# Sheet1_GMAX0505_2518_MB.net
KiCad netlist of a schematic drawn in Altium Designer
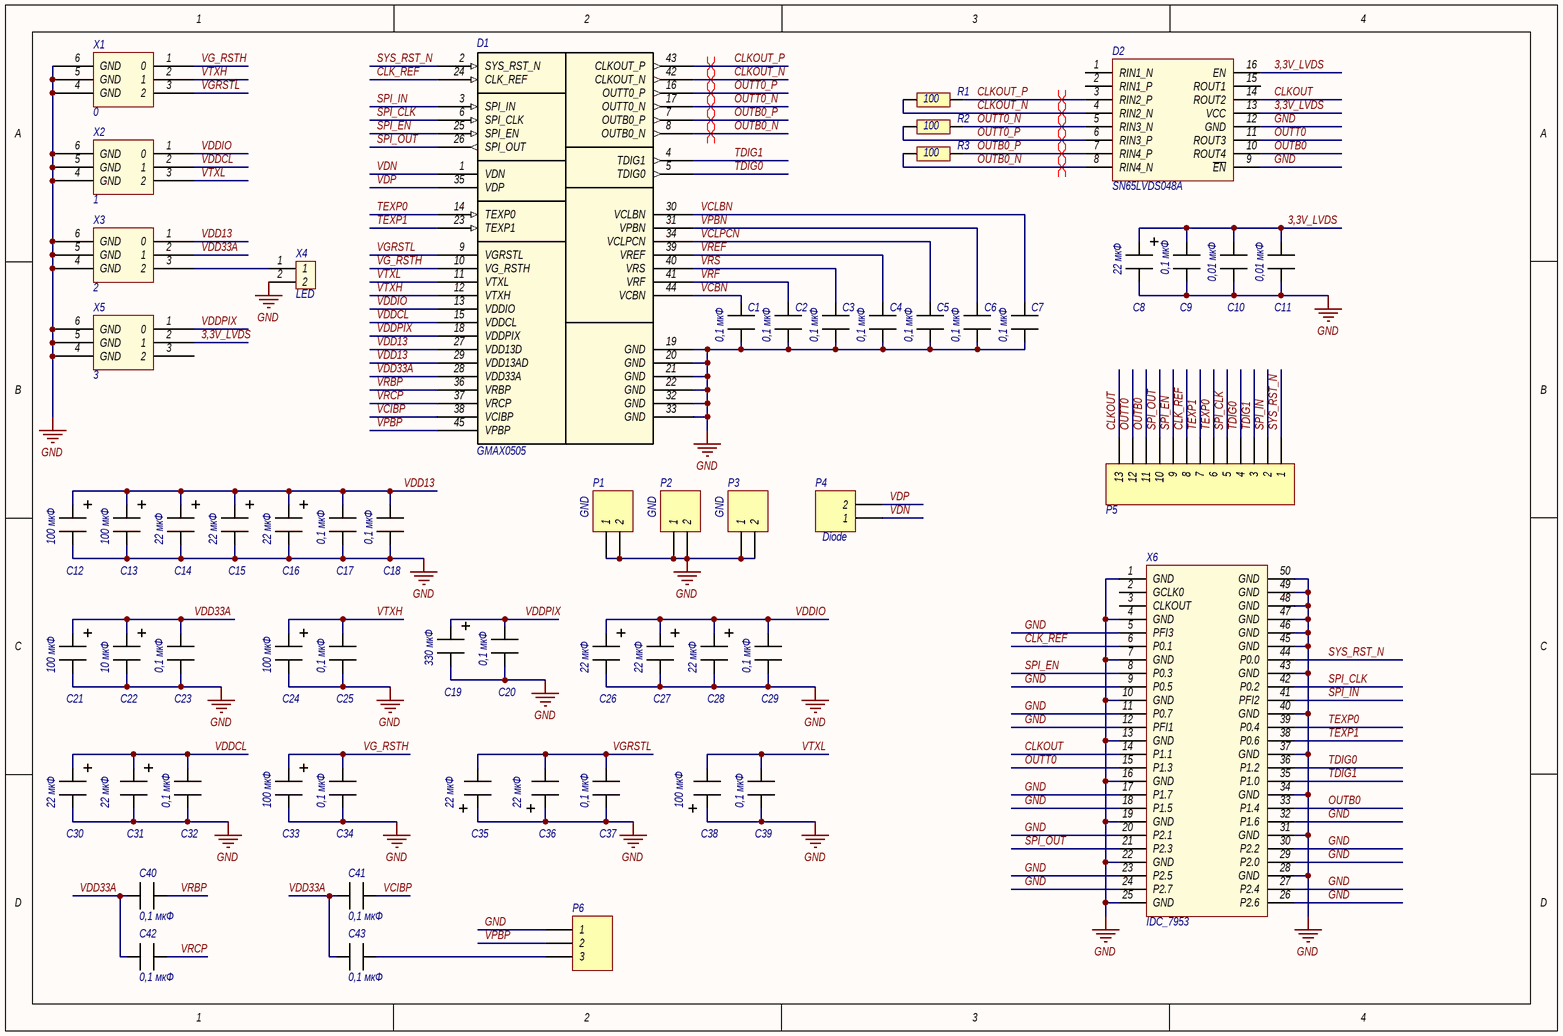
[diagram p0: Sheet1_GMAX0505_2518_MB.SchDoc]

(export (version "E")
  (design (tool "Eeschema 10.0.6"))
  (components
    (comp (ref "C1") (value "0,1 мкФ") (footprint "CAP_SMALL") (libsource (lib "Schlib") (part "CAP_SMALL")))
    (comp (ref "C2") (value "0,1 мкФ") (footprint "CAP_SMALL") (libsource (lib "Schlib") (part "CAP_SMALL")))
    (comp (ref "C3") (value "0,1 мкФ") (footprint "CAP_SMALL") (libsource (lib "Schlib") (part "CAP_SMALL")))
    (comp (ref "C4") (value "0,1 мкФ") (footprint "CAP_SMALL") (libsource (lib "Schlib") (part "CAP_SMALL")))
    (comp (ref "C5") (value "0,1 мкФ") (footprint "CAP_SMALL") (libsource (lib "Schlib") (part "CAP_SMALL")))
    (comp (ref "C6") (value "0,1 мкФ") (footprint "CAP_SMALL") (libsource (lib "Schlib") (part "CAP_SMALL")))
    (comp (ref "C7") (value "0,1 мкФ") (footprint "CAP_SMALL") (libsource (lib "Schlib") (part "CAP_SMALL")))
    (comp (ref "C8")
      (value "22 мкФ")
      (footprint "Cap_0511_electrolitic")
      (libsource (lib "Schlib") (part "Cap_electrolotoc_0511"))
    )
    (comp (ref "C9") (value "0,1 мкФ") (footprint "CAP_SMALL") (libsource (lib "Schlib") (part "CAP_SMALL")))
    (comp (ref "C10")
      (value "0,01 мкФ")
      (footprint "CAP_SMALL")
      (libsource (lib "Schlib") (part "CAP_SMALL"))
    )
    (comp (ref "C11")
      (value "0,01 мкФ")
      (footprint "CAP_SMALL")
      (libsource (lib "Schlib") (part "CAP_SMALL"))
    )
    (comp (ref "C12")
      (value "100 мкФ")
      (footprint "Cap_0612_electrolitic")
      (libsource (lib "Schlib") (part "Cap_electrolotoc_0612"))
    )
    (comp (ref "C13")
      (value "100 мкФ")
      (footprint "Cap_0612_electrolitic")
      (libsource (lib "Schlib") (part "Cap_electrolotoc_0612"))
    )
    (comp (ref "C14")
      (value "22 мкФ")
      (footprint "Cap_0511_electrolitic")
      (libsource (lib "Schlib") (part "Cap_electrolotoc_0511"))
    )
    (comp (ref "C15")
      (value "22 мкФ")
      (footprint "Cap_0511_electrolitic")
      (libsource (lib "Schlib") (part "Cap_electrolotoc_0511"))
    )
    (comp (ref "C16")
      (value "22 мкФ")
      (footprint "Cap_0511_electrolitic")
      (libsource (lib "Schlib") (part "Cap_electrolotoc_0511"))
    )
    (comp (ref "C17") (value "0,1 мкФ") (footprint "CAP_SMALL") (libsource (lib "Schlib") (part "CAP_SMALL")))
    (comp (ref "C18") (value "0,1 мкФ") (footprint "CAP_SMALL") (libsource (lib "Schlib") (part "CAP_SMALL")))
    (comp (ref "C19")
      (value "330 мкФ")
      (footprint "Cap_1013_electrolitic")
      (libsource (lib "Schlib") (part "Cap_electrolotoc_1013"))
    )
    (comp (ref "C20") (value "0,1 мкФ") (footprint "CAP_SMALL") (libsource (lib "Schlib") (part "CAP_SMALL")))
    (comp (ref "C21")
      (value "100 мкФ")
      (footprint "Cap_0612_electrolitic")
      (libsource (lib "Schlib") (part "Cap_electrolotoc_0612"))
    )
    (comp (ref "C22")
      (value "10 мкФ")
      (footprint "Cap_0511_electrolitic")
      (libsource (lib "Schlib") (part "Cap_electrolotoc_0511"))
    )
    (comp (ref "C23") (value "0,1 мкФ") (footprint "CAP_SMALL") (libsource (lib "Schlib") (part "CAP_SMALL")))
    (comp (ref "C24")
      (value "100 мкФ")
      (footprint "Cap_0612_electrolitic")
      (libsource (lib "Schlib") (part "Cap_electrolotoc_0612"))
    )
    (comp (ref "C25") (value "0,1 мкФ") (footprint "CAP_SMALL") (libsource (lib "Schlib") (part "CAP_SMALL")))
    (comp (ref "C26")
      (value "22 мкФ")
      (footprint "Cap_0511_electrolitic")
      (libsource (lib "Schlib") (part "Cap_electrolotoc_0511"))
    )
    (comp (ref "C27")
      (value "22 мкФ")
      (footprint "Cap_0511_electrolitic")
      (libsource (lib "Schlib") (part "Cap_electrolotoc_0511"))
    )
    (comp (ref "C28")
      (value "22 мкФ")
      (footprint "Cap_0511_electrolitic")
      (libsource (lib "Schlib") (part "Cap_electrolotoc_0511"))
    )
    (comp (ref "C29") (value "0,1 мкФ") (footprint "CAP_SMALL") (libsource (lib "Schlib") (part "CAP_SMALL")))
    (comp (ref "C30")
      (value "22 мкФ")
      (footprint "Cap_0511_electrolitic")
      (libsource (lib "Schlib") (part "Cap_electrolotoc_0511"))
    )
    (comp (ref "C31")
      (value "22 мкФ")
      (footprint "Cap_0511_electrolitic")
      (libsource (lib "Schlib") (part "Cap_electrolotoc_0511"))
    )
    (comp (ref "C32") (value "0,1 мкФ") (footprint "CAP_SMALL") (libsource (lib "Schlib") (part "CAP_SMALL")))
    (comp (ref "C33")
      (value "100 мкФ")
      (footprint "Cap_0612_electrolitic")
      (libsource (lib "Schlib") (part "Cap_electrolotoc_0612"))
    )
    (comp (ref "C34") (value "0,1 мкФ") (footprint "CAP_SMALL") (libsource (lib "Schlib") (part "CAP_SMALL")))
    (comp (ref "C35")
      (value "22 мкФ")
      (footprint "Cap_0511_electrolitic")
      (libsource (lib "Schlib") (part "Cap_electrolotoc_0511"))
    )
    (comp (ref "C36")
      (value "22 мкФ")
      (footprint "Cap_0511_electrolitic")
      (libsource (lib "Schlib") (part "Cap_electrolotoc_0511"))
    )
    (comp (ref "C37") (value "0,1 мкФ") (footprint "CAP_SMALL") (libsource (lib "Schlib") (part "CAP_SMALL")))
    (comp (ref "C38")
      (value "100 мкФ")
      (footprint "Cap_0612_electrolitic")
      (libsource (lib "Schlib") (part "Cap_electrolotoc_0612"))
    )
    (comp (ref "C39") (value "0,1 мкФ") (footprint "CAP_SMALL") (libsource (lib "Schlib") (part "CAP_SMALL")))
    (comp (ref "C40") (value "0,1 мкФ") (footprint "CAP_SMALL") (libsource (lib "Schlib") (part "CAP_SMALL")))
    (comp (ref "C41") (value "0,1 мкФ") (footprint "CAP_SMALL") (libsource (lib "Schlib") (part "CAP_SMALL")))
    (comp (ref "C42") (value "0,1 мкФ") (footprint "CAP_SMALL") (libsource (lib "Schlib") (part "CAP_SMALL")))
    (comp (ref "C43") (value "0,1 мкФ") (footprint "CAP_SMALL") (libsource (lib "Schlib") (part "CAP_SMALL")))
    (comp (ref "D1")
      (value "GMAX0505")
      (footprint "GMAX0505_MEZ")
      (libsource (lib "Schlib") (part "GMAX0505_MEZ"))
    )
    (comp (ref "D2")
      (value "SN65LVDS048A")
      (footprint "SN65LVDS048A (4LVDS)")
      (libsource (lib "Schlib") (part "SN65LVDS048A (4LVDS)"))
    )
    (comp (ref "P1")
      (value "GND")
      (footprint "HDR1X2")
      (description "Header, 2-Pin")
      (fields (field (name "PUBLISHER") "Altium Limited"))
      (libsource (lib "Miscellaneous Connectors") (part "Header 2"))
    )
    (comp (ref "P2")
      (value "GND")
      (footprint "HDR1X2")
      (description "Header, 2-Pin")
      (fields (field (name "PUBLISHER") "Altium Limited"))
      (libsource (lib "Miscellaneous Connectors") (part "Header 2"))
    )
    (comp (ref "P3")
      (value "GND")
      (footprint "HDR1X2")
      (description "Header, 2-Pin")
      (fields (field (name "PUBLISHER") "Altium Limited"))
      (libsource (lib "Miscellaneous Connectors") (part "Header 2"))
    )
    (comp (ref "P4")
      (value "Diode")
      (footprint "HDR1X2")
      (description "Header, 2-Pin")
      (fields (field (name "PUBLISHER") "Altium Limited"))
      (libsource (lib "") (part "Header 2_1"))
    )
    (comp (ref "P5")
      (value "Header 13")
      (footprint "HDR1X13")
      (description "Header, 13-Pin")
      (fields (field (name "PUBLISHER") "Altium Limited"))
      (libsource (lib "Miscellaneous Connectors") (part "Header 13"))
    )
    (comp (ref "P6")
      (value "VPBP")
      (footprint "HDR1X3")
      (description "Header, 3-Pin")
      (fields (field (name "PUBLISHER") "Altium Limited"))
      (libsource (lib "Miscellaneous Connectors") (part "Header 3"))
    )
    (comp (ref "R1") (value "100") (footprint "RES") (libsource (lib "Schlib") (part "RES")))
    (comp (ref "R2") (value "100") (footprint "RES") (libsource (lib "Schlib") (part "RES")))
    (comp (ref "R3") (value "100") (footprint "RES") (libsource (lib "Schlib") (part "RES")))
    (comp (ref "X1") (value "0") (footprint "POWER") (libsource (lib "Schlib") (part "POWER")))
    (comp (ref "X2") (value "1") (footprint "POWER") (libsource (lib "Schlib") (part "POWER")))
    (comp (ref "X3") (value "2") (footprint "POWER") (libsource (lib "Schlib") (part "POWER")))
    (comp (ref "X4") (value "LED") (footprint "KLEMMNIK_2") (libsource (lib "Schlib") (part "KLEMMNIK_2")))
    (comp (ref "X5") (value "3") (footprint "POWER") (libsource (lib "Schlib") (part "POWER")))
    (comp (ref "X6") (value "IDC_7953") (footprint "IDC_7953") (libsource (lib "VPL") (part "IDC_7953")))
  )
  (nets
    (net (code "1") (name "/3,3V_LVDS") (class "Default")
      (node (ref "C10") (pin "2") (pinfunction "2_2") (pintype "passive"))
      (node (ref "C11") (pin "2") (pinfunction "2_2") (pintype "passive"))
      (node (ref "C8") (pin "1") (pinfunction "1_1") (pintype "passive"))
      (node (ref "C9") (pin "2") (pinfunction "2_2") (pintype "passive"))
      (node (ref "D2") (pin "13") (pinfunction "VCC_13") (pintype "passive"))
      (node (ref "D2") (pin "16") (pinfunction "EN_16") (pintype "passive"))
      (node (ref "X5") (pin "2") (pinfunction "1_2") (pintype "passive"))
    )
    (net (code "2") (name "/CLKOUT") (class "Default")
      (node (ref "D2") (pin "14") (pinfunction "ROUT2_14") (pintype "passive"))
      (node (ref "P5") (pin "13") (pinfunction "13_13") (pintype "passive"))
      (node (ref "X6") (pin "14") (pinfunction "P1.1_14") (pintype "passive"))
    )
    (net (code "3") (name "/CLKOUT_N") (class "Default")
      (node (ref "D1") (pin "42") (pinfunction "CLKOUT_N_42") (pintype "output"))
      (node (ref "D2") (pin "4") (pinfunction "RIN2_N_4") (pintype "passive"))
      (node (ref "R1") (pin "2") (pinfunction "2_2") (pintype "passive"))
    )
    (net (code "4") (name "/CLKOUT_P") (class "Default")
      (node (ref "D1") (pin "43") (pinfunction "CLKOUT_P_43") (pintype "output"))
      (node (ref "D2") (pin "3") (pinfunction "RIN2_P_3") (pintype "passive"))
      (node (ref "R1") (pin "1") (pinfunction "1_1") (pintype "passive"))
    )
    (net (code "5") (name "/CLK_REF") (class "Default")
      (node (ref "D1") (pin "24") (pinfunction "CLK_REF_24") (pintype "input"))
      (node (ref "P5") (pin "8") (pinfunction "8_8") (pintype "passive"))
      (node (ref "X6") (pin "6") (pinfunction "P0.1_6") (pintype "passive"))
    )
    (net (code "6") (name "/OUTB0") (class "Default")
      (node (ref "D2") (pin "10") (pinfunction "ROUT4_10") (pintype "passive"))
      (node (ref "P5") (pin "11") (pinfunction "11_11") (pintype "passive"))
      (node (ref "X6") (pin "33") (pinfunction "P1.4_33") (pintype "passive"))
    )
    (net (code "7") (name "/OUTB0_N") (class "Default")
      (node (ref "D1") (pin "8") (pinfunction "OUTB0_N_8") (pintype "output"))
      (node (ref "D2") (pin "8") (pinfunction "RIN4_N_8") (pintype "passive"))
      (node (ref "R3") (pin "2") (pinfunction "2_2") (pintype "passive"))
    )
    (net (code "8") (name "/OUTB0_P") (class "Default")
      (node (ref "D1") (pin "7") (pinfunction "OUTB0_P_7") (pintype "output"))
      (node (ref "D2") (pin "7") (pinfunction "RIN4_P_7") (pintype "passive"))
      (node (ref "R3") (pin "1") (pinfunction "1_1") (pintype "passive"))
    )
    (net (code "9") (name "/OUTT0") (class "Default")
      (node (ref "D2") (pin "11") (pinfunction "ROUT3_11") (pintype "passive"))
      (node (ref "P5") (pin "12") (pinfunction "12_12") (pintype "passive"))
      (node (ref "X6") (pin "15") (pinfunction "P1.3_15") (pintype "passive"))
    )
    (net (code "10") (name "/OUTT0_N") (class "Default")
      (node (ref "D1") (pin "17") (pinfunction "OUTT0_N_17") (pintype "output"))
      (node (ref "D2") (pin "5") (pinfunction "RIN3_N_5") (pintype "passive"))
      (node (ref "R2") (pin "1") (pinfunction "1_1") (pintype "passive"))
    )
    (net (code "11") (name "/OUTT0_P") (class "Default")
      (node (ref "D1") (pin "16") (pinfunction "OUTT0_P_16") (pintype "output"))
      (node (ref "D2") (pin "6") (pinfunction "RIN3_P_6") (pintype "passive"))
      (node (ref "R2") (pin "2") (pinfunction "2_2") (pintype "passive"))
    )
    (net (code "12") (name "/SPI_CLK") (class "Default")
      (node (ref "D1") (pin "6") (pinfunction "SPI_CLK_6") (pintype "input"))
      (node (ref "P5") (pin "5") (pinfunction "5_5") (pintype "passive"))
      (node (ref "X6") (pin "42") (pinfunction "P0.2_42") (pintype "passive"))
    )
    (net (code "13") (name "/SPI_EN") (class "Default")
      (node (ref "D1") (pin "25") (pinfunction "SPI_EN_25") (pintype "input"))
      (node (ref "P5") (pin "9") (pinfunction "9_9") (pintype "passive"))
      (node (ref "X6") (pin "8") (pinfunction "P0.3_8") (pintype "passive"))
    )
    (net (code "14") (name "/SPI_IN") (class "Default")
      (node (ref "D1") (pin "3") (pinfunction "SPI_IN_3") (pintype "input"))
      (node (ref "P5") (pin "2") (pinfunction "2_2") (pintype "passive"))
      (node (ref "X6") (pin "41") (pinfunction "PFI2_41") (pintype "passive"))
    )
    (net (code "15") (name "/SPI_OUT") (class "Default")
      (node (ref "D1") (pin "26") (pinfunction "SPI_OUT_26") (pintype "output"))
      (node (ref "P5") (pin "10") (pinfunction "10_10") (pintype "passive"))
      (node (ref "X6") (pin "21") (pinfunction "P2.3_21") (pintype "passive"))
    )
    (net (code "16") (name "/SYS_RST_N") (class "Default")
      (node (ref "D1") (pin "2") (pinfunction "SYS_RST_N_2") (pintype "input"))
      (node (ref "P5") (pin "1") (pinfunction "1_1") (pintype "passive"))
      (node (ref "X6") (pin "44") (pinfunction "P0.0_44") (pintype "passive"))
    )
    (net (code "17") (name "/TDIG0") (class "Default")
      (node (ref "D1") (pin "5") (pinfunction "TDIG0_5") (pintype "output"))
      (node (ref "P5") (pin "4") (pinfunction "4_4") (pintype "passive"))
      (node (ref "X6") (pin "36") (pinfunction "P1.2_36") (pintype "passive"))
    )
    (net (code "18") (name "/TDIG1") (class "Default")
      (node (ref "D1") (pin "4") (pinfunction "TDIG1_4") (pintype "output"))
      (node (ref "P5") (pin "3") (pinfunction "3_3") (pintype "passive"))
      (node (ref "X6") (pin "35") (pinfunction "P1.0_35") (pintype "passive"))
    )
    (net (code "19") (name "/TEXP0") (class "Default")
      (node (ref "D1") (pin "14") (pinfunction "TEXP0_14") (pintype "input"))
      (node (ref "P5") (pin "6") (pinfunction "6_6") (pintype "passive"))
      (node (ref "X6") (pin "39") (pinfunction "P0.4_39") (pintype "passive"))
    )
    (net (code "20") (name "/TEXP1") (class "Default")
      (node (ref "D1") (pin "23") (pinfunction "TEXP1_23") (pintype "input"))
      (node (ref "P5") (pin "7") (pinfunction "7_7") (pintype "passive"))
      (node (ref "X6") (pin "38") (pinfunction "P0.6_38") (pintype "passive"))
    )
    (net (code "21") (name "/VCBN") (class "Default")
      (node (ref "C1") (pin "1") (pinfunction "1_1") (pintype "passive"))
      (node (ref "D1") (pin "44") (pinfunction "VCBN_44") (pintype "passive"))
    )
    (net (code "22") (name "/VCIBP") (class "Default")
      (node (ref "C41") (pin "1") (pinfunction "1_1") (pintype "passive"))
      (node (ref "D1") (pin "38") (pinfunction "VCIBP_38") (pintype "passive"))
    )
    (net (code "23") (name "/VCLBN") (class "Default")
      (node (ref "C7") (pin "1") (pinfunction "1_1") (pintype "passive"))
      (node (ref "D1") (pin "30") (pinfunction "VCLBN_30") (pintype "passive"))
    )
    (net (code "24") (name "/VCLPCN") (class "Default")
      (node (ref "C5") (pin "1") (pinfunction "1_1") (pintype "passive"))
      (node (ref "D1") (pin "34") (pinfunction "VCLPCN_34") (pintype "passive"))
    )
    (net (code "25") (name "/VDD13") (class "Default")
      (node (ref "C12") (pin "1") (pinfunction "1_1") (pintype "passive"))
      (node (ref "C13") (pin "1") (pinfunction "1_1") (pintype "passive"))
      (node (ref "C14") (pin "1") (pinfunction "1_1") (pintype "passive"))
      (node (ref "C15") (pin "1") (pinfunction "1_1") (pintype "passive"))
      (node (ref "C16") (pin "1") (pinfunction "1_1") (pintype "passive"))
      (node (ref "C17") (pin "1") (pinfunction "1_1") (pintype "passive"))
      (node (ref "C18") (pin "1") (pinfunction "1_1") (pintype "passive"))
      (node (ref "D1") (pin "27") (pinfunction "VDD13D_27") (pintype "passive"))
      (node (ref "D1") (pin "29") (pinfunction "VDD13AD_29") (pintype "passive"))
      (node (ref "X3") (pin "1") (pinfunction "0_1") (pintype "passive"))
    )
    (net (code "26") (name "/VDD33A") (class "Default")
      (node (ref "C21") (pin "1") (pinfunction "1_1") (pintype "passive"))
      (node (ref "C22") (pin "1") (pinfunction "1_1") (pintype "passive"))
      (node (ref "C23") (pin "1") (pinfunction "1_1") (pintype "passive"))
      (node (ref "C40") (pin "2") (pinfunction "2_2") (pintype "passive"))
      (node (ref "C41") (pin "2") (pinfunction "2_2") (pintype "passive"))
      (node (ref "C42") (pin "2") (pinfunction "2_2") (pintype "passive"))
      (node (ref "C43") (pin "2") (pinfunction "2_2") (pintype "passive"))
      (node (ref "D1") (pin "28") (pinfunction "VDD33A_28") (pintype "passive"))
      (node (ref "X3") (pin "2") (pinfunction "1_2") (pintype "passive"))
    )
    (net (code "27") (name "/VDDCL") (class "Default")
      (node (ref "C30") (pin "1") (pinfunction "1_1") (pintype "passive"))
      (node (ref "C31") (pin "1") (pinfunction "1_1") (pintype "passive"))
      (node (ref "C32") (pin "2") (pinfunction "2_2") (pintype "passive"))
      (node (ref "D1") (pin "15") (pinfunction "VDDCL_15") (pintype "passive"))
      (node (ref "X2") (pin "2") (pinfunction "1_2") (pintype "passive"))
    )
    (net (code "28") (name "/VDDIO") (class "Default")
      (node (ref "C26") (pin "1") (pinfunction "1_1") (pintype "passive"))
      (node (ref "C27") (pin "1") (pinfunction "1_1") (pintype "passive"))
      (node (ref "C28") (pin "1") (pinfunction "1_1") (pintype "passive"))
      (node (ref "C29") (pin "1") (pinfunction "1_1") (pintype "passive"))
      (node (ref "D1") (pin "13") (pinfunction "VDDIO_13") (pintype "passive"))
      (node (ref "X2") (pin "1") (pinfunction "0_1") (pintype "passive"))
    )
    (net (code "29") (name "/VDDPIX") (class "Default")
      (node (ref "C19") (pin "1") (pinfunction "1_1") (pintype "passive"))
      (node (ref "C20") (pin "1") (pinfunction "1_1") (pintype "passive"))
      (node (ref "D1") (pin "18") (pinfunction "VDDPIX_18") (pintype "passive"))
      (node (ref "X5") (pin "1") (pinfunction "0_1") (pintype "passive"))
    )
    (net (code "30") (name "/VDN") (class "Default")
      (node (ref "D1") (pin "1") (pinfunction "VDN_1") (pintype "passive"))
      (node (ref "P4") (pin "1") (pinfunction "1_1") (pintype "passive"))
    )
    (net (code "31") (name "/VDP") (class "Default")
      (node (ref "D1") (pin "35") (pinfunction "VDP_35") (pintype "passive"))
      (node (ref "P4") (pin "2") (pinfunction "2_2") (pintype "passive"))
    )
    (net (code "32") (name "/VGRSTL") (class "Default")
      (node (ref "C35") (pin "2") (pinfunction "2_2") (pintype "passive"))
      (node (ref "C36") (pin "2") (pinfunction "2_2") (pintype "passive"))
      (node (ref "C37") (pin "2") (pinfunction "2_2") (pintype "passive"))
      (node (ref "D1") (pin "9") (pinfunction "VGRSTL_9") (pintype "passive"))
      (node (ref "X1") (pin "3") (pinfunction "2_3") (pintype "passive"))
    )
    (net (code "33") (name "/VG_RSTH") (class "Default")
      (node (ref "C33") (pin "1") (pinfunction "1_1") (pintype "passive"))
      (node (ref "C34") (pin "1") (pinfunction "1_1") (pintype "passive"))
      (node (ref "D1") (pin "10") (pinfunction "VG_RSTH_10") (pintype "passive"))
      (node (ref "X1") (pin "1") (pinfunction "0_1") (pintype "passive"))
    )
    (net (code "34") (name "/VPBN") (class "Default")
      (node (ref "C6") (pin "1") (pinfunction "1_1") (pintype "passive"))
      (node (ref "D1") (pin "31") (pinfunction "VPBN_31") (pintype "passive"))
    )
    (net (code "35") (name "/VPBP") (class "Default")
      (node (ref "D1") (pin "45") (pinfunction "VPBP_45") (pintype "passive"))
      (node (ref "P6") (pin "2") (pinfunction "2_2") (pintype "passive"))
    )
    (net (code "36") (name "/VRBP") (class "Default")
      (node (ref "C40") (pin "1") (pinfunction "1_1") (pintype "passive"))
      (node (ref "D1") (pin "36") (pinfunction "VRBP_36") (pintype "passive"))
    )
    (net (code "37") (name "/VRCP") (class "Default")
      (node (ref "C42") (pin "1") (pinfunction "1_1") (pintype "passive"))
      (node (ref "D1") (pin "37") (pinfunction "VRCP_37") (pintype "passive"))
    )
    (net (code "38") (name "/VREF") (class "Default")
      (node (ref "C4") (pin "1") (pinfunction "1_1") (pintype "passive"))
      (node (ref "D1") (pin "39") (pinfunction "VREF_39") (pintype "passive"))
    )
    (net (code "39") (name "/VRF") (class "Default")
      (node (ref "C2") (pin "1") (pinfunction "1_1") (pintype "passive"))
      (node (ref "D1") (pin "41") (pinfunction "VRF_41") (pintype "passive"))
    )
    (net (code "40") (name "/VRS") (class "Default")
      (node (ref "C3") (pin "1") (pinfunction "1_1") (pintype "passive"))
      (node (ref "D1") (pin "40") (pinfunction "VRS_40") (pintype "passive"))
    )
    (net (code "41") (name "/VTXH") (class "Default")
      (node (ref "C24") (pin "1") (pinfunction "1_1") (pintype "passive"))
      (node (ref "C25") (pin "1") (pinfunction "1_1") (pintype "passive"))
      (node (ref "D1") (pin "12") (pinfunction "VTXH_12") (pintype "passive"))
      (node (ref "X1") (pin "2") (pinfunction "1_2") (pintype "passive"))
    )
    (net (code "42") (name "/VTXL") (class "Default")
      (node (ref "C38") (pin "2") (pinfunction "2_2") (pintype "passive"))
      (node (ref "C39") (pin "1") (pinfunction "1_1") (pintype "passive"))
      (node (ref "D1") (pin "11") (pinfunction "VTXL_11") (pintype "passive"))
      (node (ref "X2") (pin "3") (pinfunction "2_3") (pintype "passive"))
    )
    (net (code "43") (name "GND") (class "Default")
      (node (ref "C1") (pin "2") (pinfunction "2_2") (pintype "passive"))
      (node (ref "C10") (pin "1") (pinfunction "1_1") (pintype "passive"))
      (node (ref "C11") (pin "1") (pinfunction "1_1") (pintype "passive"))
      (node (ref "C12") (pin "2") (pinfunction "2_2") (pintype "passive"))
      (node (ref "C13") (pin "2") (pinfunction "2_2") (pintype "passive"))
      (node (ref "C14") (pin "2") (pinfunction "2_2") (pintype "passive"))
      (node (ref "C15") (pin "2") (pinfunction "2_2") (pintype "passive"))
      (node (ref "C16") (pin "2") (pinfunction "2_2") (pintype "passive"))
      (node (ref "C17") (pin "2") (pinfunction "2_2") (pintype "passive"))
      (node (ref "C18") (pin "2") (pinfunction "2_2") (pintype "passive"))
      (node (ref "C19") (pin "2") (pinfunction "2_2") (pintype "passive"))
      (node (ref "C2") (pin "2") (pinfunction "2_2") (pintype "passive"))
      (node (ref "C20") (pin "2") (pinfunction "2_2") (pintype "passive"))
      (node (ref "C21") (pin "2") (pinfunction "2_2") (pintype "passive"))
      (node (ref "C22") (pin "2") (pinfunction "2_2") (pintype "passive"))
      (node (ref "C23") (pin "2") (pinfunction "2_2") (pintype "passive"))
      (node (ref "C24") (pin "2") (pinfunction "2_2") (pintype "passive"))
      (node (ref "C25") (pin "2") (pinfunction "2_2") (pintype "passive"))
      (node (ref "C26") (pin "2") (pinfunction "2_2") (pintype "passive"))
      (node (ref "C27") (pin "2") (pinfunction "2_2") (pintype "passive"))
      (node (ref "C28") (pin "2") (pinfunction "2_2") (pintype "passive"))
      (node (ref "C29") (pin "2") (pinfunction "2_2") (pintype "passive"))
      (node (ref "C3") (pin "2") (pinfunction "2_2") (pintype "passive"))
      (node (ref "C30") (pin "2") (pinfunction "2_2") (pintype "passive"))
      (node (ref "C31") (pin "2") (pinfunction "2_2") (pintype "passive"))
      (node (ref "C32") (pin "1") (pinfunction "1_1") (pintype "passive"))
      (node (ref "C33") (pin "2") (pinfunction "2_2") (pintype "passive"))
      (node (ref "C34") (pin "2") (pinfunction "2_2") (pintype "passive"))
      (node (ref "C35") (pin "1") (pinfunction "1_1") (pintype "passive"))
      (node (ref "C36") (pin "1") (pinfunction "1_1") (pintype "passive"))
      (node (ref "C37") (pin "1") (pinfunction "1_1") (pintype "passive"))
      (node (ref "C38") (pin "1") (pinfunction "1_1") (pintype "passive"))
      (node (ref "C39") (pin "2") (pinfunction "2_2") (pintype "passive"))
      (node (ref "C4") (pin "2") (pinfunction "2_2") (pintype "passive"))
      (node (ref "C5") (pin "2") (pinfunction "2_2") (pintype "passive"))
      (node (ref "C6") (pin "2") (pinfunction "2_2") (pintype "passive"))
      (node (ref "C7") (pin "2") (pinfunction "2_2") (pintype "passive"))
      (node (ref "C8") (pin "2") (pinfunction "2_2") (pintype "passive"))
      (node (ref "C9") (pin "1") (pinfunction "1_1") (pintype "passive"))
      (node (ref "D1") (pin "19") (pinfunction "GND_19") (pintype "passive"))
      (node (ref "D1") (pin "20") (pinfunction "GND_20") (pintype "passive"))
      (node (ref "D1") (pin "21") (pinfunction "GND_21") (pintype "passive"))
      (node (ref "D1") (pin "22") (pinfunction "GND_22") (pintype "passive"))
      (node (ref "D1") (pin "32") (pinfunction "GND_32") (pintype "passive"))
      (node (ref "D1") (pin "33") (pinfunction "GND_33") (pintype "passive"))
      (node (ref "D2") (pin "12") (pinfunction "GND_12") (pintype "passive"))
      (node (ref "D2") (pin "9") (pinfunction "~{EN}_9") (pintype "passive"))
      (node (ref "P1") (pin "1") (pinfunction "1_1") (pintype "passive"))
      (node (ref "P1") (pin "2") (pinfunction "2_2") (pintype "passive"))
      (node (ref "P2") (pin "1") (pinfunction "1_1") (pintype "passive"))
      (node (ref "P2") (pin "2") (pinfunction "2_2") (pintype "passive"))
      (node (ref "P3") (pin "1") (pinfunction "1_1") (pintype "passive"))
      (node (ref "P3") (pin "2") (pinfunction "2_2") (pintype "passive"))
      (node (ref "P6") (pin "1") (pinfunction "1_1") (pintype "passive"))
      (node (ref "X1") (pin "4") (pinfunction "GND_4") (pintype "passive"))
      (node (ref "X1") (pin "5") (pinfunction "GND_5") (pintype "passive"))
      (node (ref "X1") (pin "6") (pinfunction "GND_6") (pintype "passive"))
      (node (ref "X2") (pin "4") (pinfunction "GND_4") (pintype "passive"))
      (node (ref "X2") (pin "5") (pinfunction "GND_5") (pintype "passive"))
      (node (ref "X2") (pin "6") (pinfunction "GND_6") (pintype "passive"))
      (node (ref "X3") (pin "4") (pinfunction "GND_4") (pintype "passive"))
      (node (ref "X3") (pin "5") (pinfunction "GND_5") (pintype "passive"))
      (node (ref "X3") (pin "6") (pinfunction "GND_6") (pintype "passive"))
      (node (ref "X4") (pin "2") (pinfunction "2_2") (pintype "passive"))
      (node (ref "X5") (pin "4") (pinfunction "GND_4") (pintype "passive"))
      (node (ref "X5") (pin "5") (pinfunction "GND_5") (pintype "passive"))
      (node (ref "X5") (pin "6") (pinfunction "GND_6") (pintype "passive"))
      (node (ref "X6") (pin "1") (pinfunction "GND_1") (pintype "passive"))
      (node (ref "X6") (pin "10") (pinfunction "GND_10") (pintype "passive"))
      (node (ref "X6") (pin "11") (pinfunction "P0.7_11") (pintype "passive"))
      (node (ref "X6") (pin "12") (pinfunction "PFI1_12") (pintype "passive"))
      (node (ref "X6") (pin "13") (pinfunction "GND_13") (pintype "passive"))
      (node (ref "X6") (pin "16") (pinfunction "GND_16") (pintype "passive"))
      (node (ref "X6") (pin "17") (pinfunction "P1.7_17") (pintype "passive"))
      (node (ref "X6") (pin "18") (pinfunction "P1.5_18") (pintype "passive"))
      (node (ref "X6") (pin "19") (pinfunction "GND_19") (pintype "passive"))
      (node (ref "X6") (pin "20") (pinfunction "P2.1_20") (pintype "passive"))
      (node (ref "X6") (pin "22") (pinfunction "GND_22") (pintype "passive"))
      (node (ref "X6") (pin "23") (pinfunction "P2.5_23") (pintype "passive"))
      (node (ref "X6") (pin "24") (pinfunction "P2.7_24") (pintype "passive"))
      (node (ref "X6") (pin "25") (pinfunction "GND_25") (pintype "passive"))
      (node (ref "X6") (pin "26") (pinfunction "P2.6_26") (pintype "passive"))
      (node (ref "X6") (pin "27") (pinfunction "P2.4_27") (pintype "passive"))
      (node (ref "X6") (pin "28") (pinfunction "GND_28") (pintype "passive"))
      (node (ref "X6") (pin "29") (pinfunction "P2.0_29") (pintype "passive"))
      (node (ref "X6") (pin "30") (pinfunction "P2.2_30") (pintype "passive"))
      (node (ref "X6") (pin "31") (pinfunction "GND_31") (pintype "passive"))
      (node (ref "X6") (pin "32") (pinfunction "P1.6_32") (pintype "passive"))
      (node (ref "X6") (pin "34") (pinfunction "GND_34") (pintype "passive"))
      (node (ref "X6") (pin "37") (pinfunction "GND_37") (pintype "passive"))
      (node (ref "X6") (pin "4") (pinfunction "GND_4") (pintype "passive"))
      (node (ref "X6") (pin "40") (pinfunction "GND_40") (pintype "passive"))
      (node (ref "X6") (pin "43") (pinfunction "GND_43") (pintype "passive"))
      (node (ref "X6") (pin "45") (pinfunction "GND_45") (pintype "passive"))
      (node (ref "X6") (pin "46") (pinfunction "GND_46") (pintype "passive"))
      (node (ref "X6") (pin "47") (pinfunction "GND_47") (pintype "passive"))
      (node (ref "X6") (pin "48") (pinfunction "GND_48") (pintype "passive"))
      (node (ref "X6") (pin "49") (pinfunction "GND_49") (pintype "passive"))
      (node (ref "X6") (pin "5") (pinfunction "PFI3_5") (pintype "passive"))
      (node (ref "X6") (pin "50") (pinfunction "GND_50") (pintype "passive"))
      (node (ref "X6") (pin "7") (pinfunction "GND_7") (pintype "passive"))
      (node (ref "X6") (pin "9") (pinfunction "P0.5_9") (pintype "passive"))
    )
    (net (code "44") (name "Net-(C43-Pad1)") (class "Default")
      (node (ref "C43") (pin "1") (pinfunction "1_1") (pintype "passive"))
      (node (ref "P6") (pin "3") (pinfunction "3_3") (pintype "passive"))
    )
    (net (code "45") (name "Net-(X3-2)") (class "Default")
      (node (ref "X3") (pin "3") (pinfunction "2_3") (pintype "passive"))
      (node (ref "X4") (pin "1") (pinfunction "1_1") (pintype "passive"))
    )
    (net (code "46") (name "unconnected-(D2-RIN1_N-Pad1)") (class "Default")
      (node (ref "D2") (pin "1") (pinfunction "RIN1_N_1") (pintype "passive"))
    )
    (net (code "47") (name "unconnected-(D2-RIN1_P-Pad2)") (class "Default")
      (node (ref "D2") (pin "2") (pinfunction "RIN1_P_2") (pintype "passive"))
    )
    (net (code "48") (name "unconnected-(D2-ROUT1-Pad15)") (class "Default")
      (node (ref "D2") (pin "15") (pinfunction "ROUT1_15") (pintype "passive"))
    )
    (net (code "49") (name "unconnected-(X5-2-Pad3)") (class "Default")
      (node (ref "X5") (pin "3") (pinfunction "2_3") (pintype "passive"))
    )
    (net (code "50") (name "unconnected-(X6-CLKOUT-Pad3)") (class "Default")
      (node (ref "X6") (pin "3") (pinfunction "CLKOUT_3") (pintype "passive"))
    )
    (net (code "51") (name "unconnected-(X6-GCLK0-Pad2)") (class "Default")
      (node (ref "X6") (pin "2") (pinfunction "GCLK0_2") (pintype "passive"))
    )
  )
)
